# SilverDollarGame.net
KiCad netlist of a schematic drawn in EAGLE
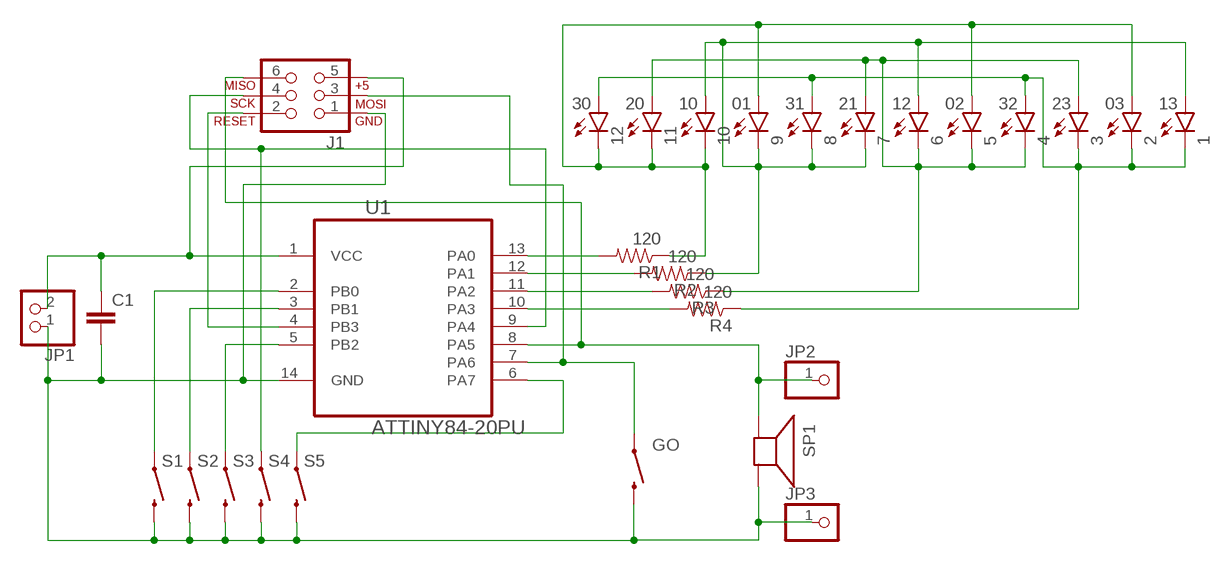
[diagram p0: schematic, sheet 1]

(export (version "E")
  (design (tool "Eeschema 10.0.6"))
  (components
    (comp (ref "1")
      (value "LED3MM")
      (footprint "eagle-import:LED3MM")
      (libsource (lib "eagle-import") (part "LED3MM"))
    )
    (comp (ref "2")
      (value "LED3MM")
      (footprint "eagle-import:LED3MM")
      (libsource (lib "eagle-import") (part "LED3MM"))
    )
    (comp (ref "3")
      (value "LED3MM")
      (footprint "eagle-import:LED3MM")
      (libsource (lib "eagle-import") (part "LED3MM"))
    )
    (comp (ref "4")
      (value "LED3MM")
      (footprint "eagle-import:LED3MM")
      (libsource (lib "eagle-import") (part "LED3MM"))
    )
    (comp (ref "5")
      (value "LED3MM")
      (footprint "eagle-import:LED3MM")
      (libsource (lib "eagle-import") (part "LED3MM"))
    )
    (comp (ref "6")
      (value "LED3MM")
      (footprint "eagle-import:LED3MM")
      (libsource (lib "eagle-import") (part "LED3MM"))
    )
    (comp (ref "7")
      (value "LED3MM")
      (footprint "eagle-import:LED3MM")
      (libsource (lib "eagle-import") (part "LED3MM"))
    )
    (comp (ref "8")
      (value "LED3MM")
      (footprint "eagle-import:LED3MM")
      (libsource (lib "eagle-import") (part "LED3MM"))
    )
    (comp (ref "9")
      (value "LED3MM")
      (footprint "eagle-import:LED3MM")
      (libsource (lib "eagle-import") (part "LED3MM"))
    )
    (comp (ref "10")
      (value "LED3MM")
      (footprint "eagle-import:LED3MM")
      (libsource (lib "eagle-import") (part "LED3MM"))
    )
    (comp (ref "11")
      (value "LED3MM")
      (footprint "eagle-import:LED3MM")
      (libsource (lib "eagle-import") (part "LED3MM"))
    )
    (comp (ref "12")
      (value "LED3MM")
      (footprint "eagle-import:LED3MM")
      (libsource (lib "eagle-import") (part "LED3MM"))
    )
    (comp (ref "C1")
      (value "0.1UF-50V-20%(PTH)KIT-EZ")
      (footprint "eagle-import:CAP-PTH-SMALL-KIT")
      (libsource (lib "eagle-import") (part "0.1UF-50V-20%(PTH)KIT-EZ"))
    )
    (comp (ref "GO")
      (value "SWITCH-MOMENTARY-2PTH")
      (footprint "eagle-import:TACTILE-PTH")
      (libsource (lib "eagle-import") (part "SWITCH-MOMENTARY-2PTH"))
    )
    (comp (ref "J1")
      (value "AVR_SPI_PRG_6TESTPOINTS")
      (footprint "eagle-import:2X3_TEST_POINTS")
      (libsource (lib "eagle-import") (part "AVR_SPI_PRG_6TESTPOINTS"))
    )
    (comp (ref "JP1")
      (value "HEADER-1X2ROUND")
      (footprint "eagle-import:1X02_ROUND")
      (libsource (lib "eagle-import") (part "HEADER-1X2ROUND"))
    )
    (comp (ref "JP2")
      (value "PINHD-1X1CB")
      (footprint "eagle-import:1X01-CLEANBIG")
      (libsource (lib "eagle-import") (part "PINHD-1X1CB"))
    )
    (comp (ref "JP3")
      (value "PINHD-1X1CB")
      (footprint "eagle-import:1X01-CLEANBIG")
      (libsource (lib "eagle-import") (part "PINHD-1X1CB"))
    )
    (comp (ref "R1")
      (value "120")
      (footprint "eagle-import:AXIAL-0.3")
      (libsource (lib "eagle-import") (part "RESISTORAXIAL-0.3"))
    )
    (comp (ref "R2")
      (value "120")
      (footprint "eagle-import:AXIAL-0.3")
      (libsource (lib "eagle-import") (part "RESISTORAXIAL-0.3"))
    )
    (comp (ref "R3")
      (value "120")
      (footprint "eagle-import:AXIAL-0.3")
      (libsource (lib "eagle-import") (part "RESISTORAXIAL-0.3"))
    )
    (comp (ref "R4")
      (value "120")
      (footprint "eagle-import:AXIAL-0.3")
      (libsource (lib "eagle-import") (part "RESISTORAXIAL-0.3"))
    )
    (comp (ref "S1")
      (value "SWITCH-MOMENTARY-2PTH")
      (footprint "eagle-import:TACTILE-PTH")
      (libsource (lib "eagle-import") (part "SWITCH-MOMENTARY-2PTH"))
    )
    (comp (ref "S2")
      (value "SWITCH-MOMENTARY-2PTH")
      (footprint "eagle-import:TACTILE-PTH")
      (libsource (lib "eagle-import") (part "SWITCH-MOMENTARY-2PTH"))
    )
    (comp (ref "S3")
      (value "SWITCH-MOMENTARY-2PTH")
      (footprint "eagle-import:TACTILE-PTH")
      (libsource (lib "eagle-import") (part "SWITCH-MOMENTARY-2PTH"))
    )
    (comp (ref "S4")
      (value "SWITCH-MOMENTARY-2PTH")
      (footprint "eagle-import:TACTILE-PTH")
      (libsource (lib "eagle-import") (part "SWITCH-MOMENTARY-2PTH"))
    )
    (comp (ref "S5")
      (value "SWITCH-MOMENTARY-2PTH")
      (footprint "eagle-import:TACTILE-PTH")
      (libsource (lib "eagle-import") (part "SWITCH-MOMENTARY-2PTH"))
    )
    (comp (ref "SP1")
      (value "ABT-402-RC")
      (footprint "eagle-import:AL60P")
      (libsource (lib "eagle-import") (part "SPEAKER/AL60P"))
    )
    (comp (ref "U1")
      (value "ATTINY84-20PU")
      (footprint "eagle-import:DIP254P762X533-14")
      (libsource (lib "eagle-import") (part "ATTINY84-20PU"))
    )
  )
  (nets
    (net (code "1") (name "Net-(1-C)") (class "Default")
      (node (ref "1") (pin "K") (pinfunction "C_K") (pintype "passive"))
      (node (ref "12") (pin "A") (pinfunction "A_A") (pintype "passive"))
      (node (ref "2") (pin "K") (pinfunction "C_K") (pintype "passive"))
      (node (ref "3") (pin "K") (pinfunction "C_K") (pintype "passive"))
      (node (ref "4") (pin "A") (pinfunction "A_A") (pintype "passive"))
      (node (ref "8") (pin "A") (pinfunction "A_A") (pintype "passive"))
      (node (ref "R4") (pin "P$1") (pinfunction "1_P$1") (pintype "passive"))
    )
    (net (code "2") (name "Net-(4-C)") (class "Default")
      (node (ref "11") (pin "A") (pinfunction "A_A") (pintype "passive"))
      (node (ref "3") (pin "A") (pinfunction "A_A") (pintype "passive"))
      (node (ref "4") (pin "K") (pinfunction "C_K") (pintype "passive"))
      (node (ref "5") (pin "K") (pinfunction "C_K") (pintype "passive"))
      (node (ref "6") (pin "K") (pinfunction "C_K") (pintype "passive"))
      (node (ref "7") (pin "A") (pinfunction "A_A") (pintype "passive"))
      (node (ref "R3") (pin "P$1") (pinfunction "1_P$1") (pintype "passive"))
    )
    (net (code "3") (name "Net-(7-C)") (class "Default")
      (node (ref "1") (pin "A") (pinfunction "A_A") (pintype "passive"))
      (node (ref "10") (pin "A") (pinfunction "A_A") (pintype "passive"))
      (node (ref "6") (pin "A") (pinfunction "A_A") (pintype "passive"))
      (node (ref "7") (pin "K") (pinfunction "C_K") (pintype "passive"))
      (node (ref "8") (pin "K") (pinfunction "C_K") (pintype "passive"))
      (node (ref "9") (pin "K") (pinfunction "C_K") (pintype "passive"))
      (node (ref "R2") (pin "P$1") (pinfunction "1_P$1") (pintype "passive"))
    )
    (net (code "4") (name "Net-(10-C)") (class "Default")
      (node (ref "10") (pin "K") (pinfunction "C_K") (pintype "passive"))
      (node (ref "11") (pin "K") (pinfunction "C_K") (pintype "passive"))
      (node (ref "12") (pin "K") (pinfunction "C_K") (pintype "passive"))
      (node (ref "2") (pin "A") (pinfunction "A_A") (pintype "passive"))
      (node (ref "5") (pin "A") (pinfunction "A_A") (pintype "passive"))
      (node (ref "9") (pin "A") (pinfunction "A_A") (pintype "passive"))
      (node (ref "R1") (pin "P$1") (pinfunction "1_P$1") (pintype "passive"))
    )
    (net (code "5") (name "Net-(GO-2)") (class "Default")
      (node (ref "C1") (pin "2") (pinfunction "2_2") (pintype "passive"))
      (node (ref "GO") (pin "3") (pinfunction "2_3") (pintype "passive"))
      (node (ref "J1") (pin "1") (pinfunction "1_1") (pintype "passive"))
      (node (ref "JP1") (pin "1") (pinfunction "1_1") (pintype "passive"))
      (node (ref "JP3") (pin "1") (pinfunction "1_1") (pintype "passive"))
      (node (ref "S1") (pin "3") (pinfunction "2_3") (pintype "passive"))
      (node (ref "S2") (pin "3") (pinfunction "2_3") (pintype "passive"))
      (node (ref "S3") (pin "3") (pinfunction "2_3") (pintype "passive"))
      (node (ref "S4") (pin "3") (pinfunction "2_3") (pintype "passive"))
      (node (ref "S5") (pin "3") (pinfunction "2_3") (pintype "passive"))
      (node (ref "SP1") (pin "2") (pinfunction "-_2") (pintype "passive"))
      (node (ref "U1") (pin "14") (pinfunction "GND_14") (pintype "passive"))
    )
    (net (code "6") (name "Net-(R1-2)") (class "Default")
      (node (ref "R1") (pin "P$2") (pinfunction "2_P$2") (pintype "passive"))
      (node (ref "U1") (pin "13") (pinfunction "PA0_13") (pintype "bidirectional"))
    )
    (net (code "7") (name "Net-(R2-2)") (class "Default")
      (node (ref "R2") (pin "P$2") (pinfunction "2_P$2") (pintype "passive"))
      (node (ref "U1") (pin "12") (pinfunction "PA1_12") (pintype "bidirectional"))
    )
    (net (code "8") (name "Net-(R3-2)") (class "Default")
      (node (ref "R3") (pin "P$2") (pinfunction "2_P$2") (pintype "passive"))
      (node (ref "U1") (pin "11") (pinfunction "PA2_11") (pintype "bidirectional"))
    )
    (net (code "9") (name "Net-(R4-2)") (class "Default")
      (node (ref "R4") (pin "P$2") (pinfunction "2_P$2") (pintype "passive"))
      (node (ref "U1") (pin "10") (pinfunction "PA3_10") (pintype "bidirectional"))
    )
    (net (code "10") (name "Net-(SP1-+)") (class "Default")
      (node (ref "J1") (pin "6") (pinfunction "6_6") (pintype "passive"))
      (node (ref "JP2") (pin "1") (pinfunction "1_1") (pintype "passive"))
      (node (ref "SP1") (pin "1") (pinfunction "+_1") (pintype "passive"))
      (node (ref "U1") (pin "8") (pinfunction "PA5_8") (pintype "bidirectional"))
    )
    (net (code "11") (name "Net-(U1-PA4)") (class "Default")
      (node (ref "J1") (pin "4") (pinfunction "4_4") (pintype "passive"))
      (node (ref "S4") (pin "1") (pinfunction "1_1") (pintype "passive"))
      (node (ref "U1") (pin "9") (pinfunction "PA4_9") (pintype "bidirectional"))
    )
    (net (code "12") (name "Net-(U1-PA6)") (class "Default")
      (node (ref "GO") (pin "1") (pinfunction "1_1") (pintype "passive"))
      (node (ref "J1") (pin "3") (pinfunction "3_3") (pintype "passive"))
      (node (ref "U1") (pin "7") (pinfunction "PA6_7") (pintype "bidirectional"))
    )
    (net (code "13") (name "Net-(U1-PA7)") (class "Default")
      (node (ref "S5") (pin "1") (pinfunction "1_1") (pintype "passive"))
      (node (ref "U1") (pin "6") (pinfunction "PA7_6") (pintype "bidirectional"))
    )
    (net (code "14") (name "Net-(U1-PB0)") (class "Default")
      (node (ref "S1") (pin "1") (pinfunction "1_1") (pintype "passive"))
      (node (ref "U1") (pin "2") (pinfunction "PB0_2") (pintype "bidirectional"))
    )
    (net (code "15") (name "Net-(U1-PB1)") (class "Default")
      (node (ref "S2") (pin "1") (pinfunction "1_1") (pintype "passive"))
      (node (ref "U1") (pin "3") (pinfunction "PB1_3") (pintype "bidirectional"))
    )
    (net (code "16") (name "Net-(U1-PB2)") (class "Default")
      (node (ref "S3") (pin "1") (pinfunction "1_1") (pintype "passive"))
      (node (ref "U1") (pin "5") (pinfunction "PB2_5") (pintype "bidirectional"))
    )
    (net (code "17") (name "Net-(U1-PB3)") (class "Default")
      (node (ref "J1") (pin "2") (pinfunction "2_2") (pintype "passive"))
      (node (ref "U1") (pin "4") (pinfunction "PB3_4") (pintype "bidirectional"))
    )
    (net (code "18") (name "Net-(U1-VCC)") (class "Default")
      (node (ref "C1") (pin "1") (pinfunction "1_1") (pintype "passive"))
      (node (ref "J1") (pin "5") (pinfunction "5_5") (pintype "passive"))
      (node (ref "JP1") (pin "2") (pinfunction "2_2") (pintype "passive"))
      (node (ref "U1") (pin "1") (pinfunction "VCC_1") (pintype "power_in"))
    )
  )
)
